# blinkm_mk2_3535ab.net
KiCad netlist of a schematic drawn in EAGLE
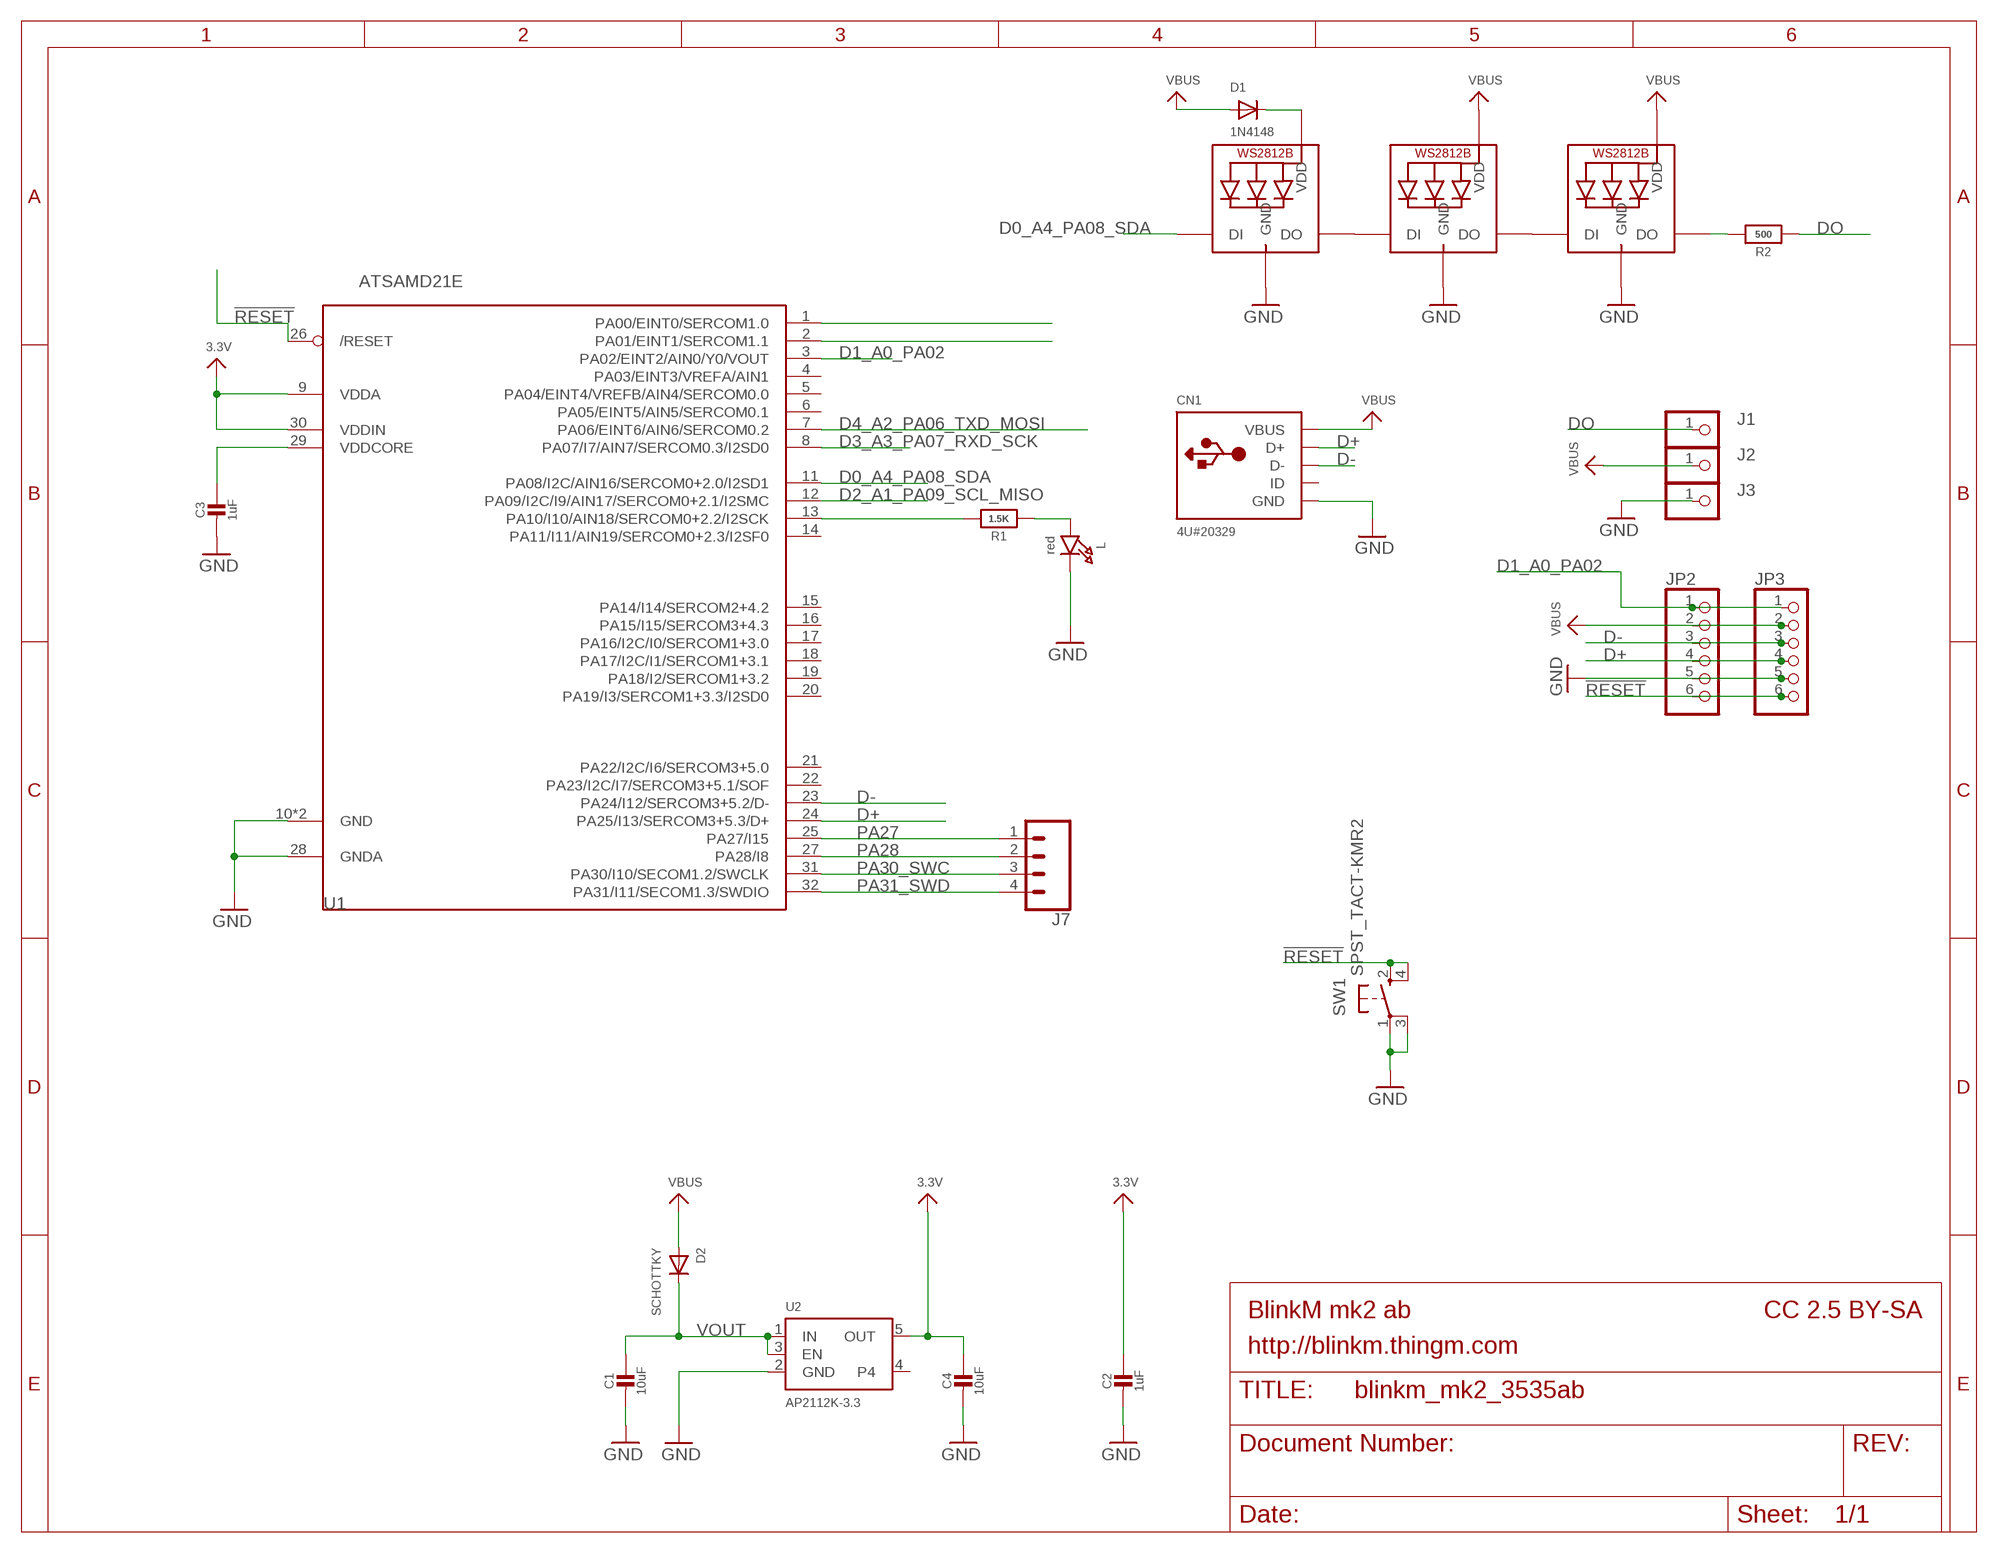
[diagram p0: schematic, sheet 1]

(export (version "E")
  (design (tool "Eeschema 10.0.6"))
  (components
    (comp (ref "C1")
      (value "10uF")
      (footprint "eagle-import:_0402")
      (libsource (lib "eagle-import") (part "CAP_CERAMIC_0402"))
    )
    (comp (ref "C2")
      (value "1uF")
      (footprint "eagle-import:_0402")
      (libsource (lib "eagle-import") (part "CAP_CERAMIC_0402"))
    )
    (comp (ref "C3")
      (value "1uF")
      (footprint "eagle-import:_0402")
      (libsource (lib "eagle-import") (part "CAP_CERAMIC_0402"))
    )
    (comp (ref "C4")
      (value "10uF")
      (footprint "eagle-import:_0402")
      (libsource (lib "eagle-import") (part "CAP_CERAMIC_0402"))
    )
    (comp (ref "CN1")
      (value "4U#20329")
      (footprint "eagle-import:4UCONN_20329_V2")
      (libsource (lib "eagle-import") (part "USB_MICRO_20329_V2"))
    )
    (comp (ref "D1")
      (value "1N4148")
      (footprint "eagle-import:SOD-523")
      (libsource (lib "eagle-import") (part "adafruit_420_DIODESOD-523"))
    )
    (comp (ref "D2")
      (value "SCHOTTKY")
      (footprint "eagle-import:SOD-523")
      (libsource (lib "eagle-import") (part "DIODESOD-523"))
    )
    (comp (ref "J1")
      (value "PINHD-1X1")
      (footprint "eagle-import:1X01")
      (libsource (lib "eagle-import") (part "PINHD-1X1"))
    )
    (comp (ref "J2")
      (value "PINHD-1X1")
      (footprint "eagle-import:1X01")
      (libsource (lib "eagle-import") (part "PINHD-1X1"))
    )
    (comp (ref "J3")
      (value "PINHD-1X1")
      (footprint "eagle-import:1X01")
      (libsource (lib "eagle-import") (part "PINHD-1X1"))
    )
    (comp (ref "J7")
      (value "CONN_041X04_NO_SILK")
      (footprint "eagle-import:1X04_NO_SILK")
      (libsource (lib "eagle-import") (part "CONN_041X04_NO_SILK"))
    )
    (comp (ref "JP2")
      (value "PINHD-1X6CLEAN")
      (footprint "eagle-import:1X06-CLEAN")
      (libsource (lib "eagle-import") (part "PINHD-1X6CLEAN"))
    )
    (comp (ref "JP3")
      (value "PINHD-1X6CLEAN")
      (footprint "eagle-import:1X06-CLEAN")
      (libsource (lib "eagle-import") (part "PINHD-1X6CLEAN"))
    )
    (comp (ref "L")
      (value "red")
      (footprint "eagle-import:CHIPLED_0603_NOOUTLINE")
      (libsource (lib "eagle-import") (part "LED0603_NOOUTLINE"))
    )
    (comp (ref "L1")
      (value "WS2812B3535")
      (footprint "eagle-import:LED3535")
      (libsource (lib "eagle-import") (part "WS2812B3535"))
    )
    (comp (ref "L2")
      (value "WS2812B3535")
      (footprint "eagle-import:LED3535")
      (libsource (lib "eagle-import") (part "WS2812B3535"))
    )
    (comp (ref "L3")
      (value "WS2812B3535")
      (footprint "eagle-import:LED3535")
      (libsource (lib "eagle-import") (part "WS2812B3535"))
    )
    (comp (ref "R1")
      (value "1.5K")
      (footprint "eagle-import:_0402")
      (libsource (lib "eagle-import") (part "RESISTOR_0402"))
    )
    (comp (ref "R2")
      (value "500")
      (footprint "eagle-import:_0402")
      (libsource (lib "eagle-import") (part "RESISTOR_0402"))
    )
    (comp (ref "SW1")
      (value "SPST_TACT-KMR2")
      (footprint "eagle-import:KMR2")
      (libsource (lib "eagle-import") (part "SPST_TACT-KMR2"))
    )
    (comp (ref "U1")
      (value "ATSAMD21E")
      (footprint "eagle-import:QFN32_5MM")
      (libsource (lib "eagle-import") (part "ATSAMD21E"))
    )
    (comp (ref "U2")
      (value "AP2112K-3.3")
      (footprint "eagle-import:SOT23-5")
      (libsource (lib "eagle-import") (part "VREG_SOT23-5"))
    )
  )
  (nets
    (net (code "1") (name "/D+") (class "Default")
      (node (ref "CN1") (pin "D+") (pinfunction "D+_D+") (pintype "bidirectional"))
      (node (ref "JP2") (pin "4") (pinfunction "4_4") (pintype "passive"))
      (node (ref "JP3") (pin "4") (pinfunction "4_4") (pintype "passive"))
      (node (ref "U1") (pin "24") (pinfunction "PA25/I13/SERCOM3+5.3/D+_24") (pintype "bidirectional"))
    )
    (net (code "2") (name "/D-") (class "Default")
      (node (ref "CN1") (pin "D-") (pinfunction "D-_D-") (pintype "bidirectional"))
      (node (ref "JP2") (pin "3") (pinfunction "3_3") (pintype "passive"))
      (node (ref "JP3") (pin "3") (pinfunction "3_3") (pintype "passive"))
      (node (ref "U1") (pin "23") (pinfunction "PA24/I12/SERCOM3+5.2/D-_23") (pintype "bidirectional"))
    )
    (net (code "3") (name "/D0_A4_PA08_SDA") (class "Default")
      (node (ref "L1") (pin "1") (pinfunction "DI_1") (pintype "input"))
      (node (ref "U1") (pin "11") (pinfunction "PA08/I2C/AIN16/SERCOM0+2.0/I2SD1_11") (pintype "bidirectional"))
    )
    (net (code "4") (name "/D1_A0_PA02") (class "Default")
      (node (ref "JP2") (pin "1") (pinfunction "1_1") (pintype "passive"))
      (node (ref "JP3") (pin "1") (pinfunction "1_1") (pintype "passive"))
      (node (ref "U1") (pin "3") (pinfunction "PA02/EINT2/AIN0/Y0/VOUT_3") (pintype "bidirectional"))
    )
    (net (code "5") (name "/D2_A1_PA09_SCL_MISO") (class "Default")
      (node (ref "U1") (pin "12") (pinfunction "PA09/I2C/I9/AIN17/SERCOM0+2.1/I2SMC_12") (pintype "bidirectional"))
    )
    (net (code "6") (name "/D3_A3_PA07_RXD_SCK") (class "Default")
      (node (ref "U1") (pin "8") (pinfunction "PA07/I7/AIN7/SERCOM0.3/I2SD0_8") (pintype "bidirectional"))
    )
    (net (code "7") (name "/D4_A2_PA06_TXD_MOSI") (class "Default")
      (node (ref "U1") (pin "7") (pinfunction "PA06/EINT6/AIN6/SERCOM0.2_7") (pintype "bidirectional"))
    )
    (net (code "8") (name "/DO") (class "Default")
      (node (ref "J1") (pin "1") (pinfunction "1_1") (pintype "passive"))
      (node (ref "R2") (pin "1") (pinfunction "1_1") (pintype "passive"))
    )
    (net (code "9") (name "/PA27") (class "Default")
      (node (ref "J7") (pin "1") (pinfunction "1_1") (pintype "passive"))
      (node (ref "U1") (pin "25") (pinfunction "PA27/I15_25") (pintype "bidirectional"))
    )
    (net (code "10") (name "/PA28") (class "Default")
      (node (ref "J7") (pin "2") (pinfunction "2_2") (pintype "passive"))
      (node (ref "U1") (pin "27") (pinfunction "PA28/I8_27") (pintype "bidirectional"))
    )
    (net (code "11") (name "/PA30_SWC") (class "Default")
      (node (ref "J7") (pin "3") (pinfunction "3_3") (pintype "passive"))
      (node (ref "U1") (pin "31") (pinfunction "PA30/I10/SECOM1.2/SWCLK_31") (pintype "bidirectional"))
    )
    (net (code "12") (name "/PA31_SWD") (class "Default")
      (node (ref "J7") (pin "4") (pinfunction "4_4") (pintype "passive"))
      (node (ref "U1") (pin "32") (pinfunction "PA31/I11/SECOM1.3/SWDIO_32") (pintype "bidirectional"))
    )
    (net (code "13") (name "/VOUT") (class "Default")
      (node (ref "C1") (pin "1") (pinfunction "1_1") (pintype "passive"))
      (node (ref "D2") (pin "K") (pinfunction "C_K") (pintype "passive"))
      (node (ref "U2") (pin "1") (pinfunction "IN_1") (pintype "power_in"))
      (node (ref "U2") (pin "3") (pinfunction "EN_3") (pintype "input"))
    )
    (net (code "14") (name "/~{RESET}") (class "Default")
      (node (ref "JP2") (pin "6") (pinfunction "6_6") (pintype "passive"))
      (node (ref "JP3") (pin "6") (pinfunction "6_6") (pintype "passive"))
      (node (ref "SW1") (pin "2") (pinfunction "S_2") (pintype "passive"))
      (node (ref "SW1") (pin "4") (pinfunction "S1_4") (pintype "passive"))
      (node (ref "U1") (pin "26") (pinfunction "/RESET_26") (pintype "bidirectional"))
    )
    (net (code "15") (name "3.3V") (class "Default")
      (node (ref "C2") (pin "1") (pinfunction "1_1") (pintype "passive"))
      (node (ref "C4") (pin "1") (pinfunction "1_1") (pintype "passive"))
      (node (ref "U1") (pin "30") (pinfunction "VDDIN_30") (pintype "power_in"))
      (node (ref "U1") (pin "9") (pinfunction "VDDA_9") (pintype "power_in"))
      (node (ref "U2") (pin "5") (pinfunction "OUT_5") (pintype "power_in"))
    )
    (net (code "16") (name "GND") (class "Default")
      (node (ref "C1") (pin "2") (pinfunction "2_2") (pintype "passive"))
      (node (ref "C2") (pin "2") (pinfunction "2_2") (pintype "passive"))
      (node (ref "C3") (pin "2") (pinfunction "2_2") (pintype "passive"))
      (node (ref "C4") (pin "2") (pinfunction "2_2") (pintype "passive"))
      (node (ref "CN1") (pin "BASE@1") (pinfunction "GND_BASE@1") (pintype "power_in"))
      (node (ref "CN1") (pin "BASE@2") (pinfunction "GND_BASE@2") (pintype "power_in"))
      (node (ref "CN1") (pin "GND") (pinfunction "GND_GND") (pintype "power_in"))
      (node (ref "CN1") (pin "SPRT@1") (pinfunction "GND_SPRT@1") (pintype "power_in"))
      (node (ref "CN1") (pin "SPRT@2") (pinfunction "GND_SPRT@2") (pintype "power_in"))
      (node (ref "CN1") (pin "SPRT@3") (pinfunction "GND_SPRT@3") (pintype "power_in"))
      (node (ref "CN1") (pin "SPRT@4") (pinfunction "GND_SPRT@4") (pintype "power_in"))
      (node (ref "J3") (pin "1") (pinfunction "1_1") (pintype "passive"))
      (node (ref "JP2") (pin "5") (pinfunction "5_5") (pintype "passive"))
      (node (ref "JP3") (pin "5") (pinfunction "5_5") (pintype "passive"))
      (node (ref "L") (pin "C") (pinfunction "C_C") (pintype "passive"))
      (node (ref "L1") (pin "4") (pinfunction "GND_4") (pintype "power_in"))
      (node (ref "L2") (pin "4") (pinfunction "GND_4") (pintype "power_in"))
      (node (ref "L3") (pin "4") (pinfunction "GND_4") (pintype "power_in"))
      (node (ref "SW1") (pin "1") (pinfunction "P_1") (pintype "passive"))
      (node (ref "SW1") (pin "3") (pinfunction "P1_3") (pintype "passive"))
      (node (ref "U1") (pin "10") (pinfunction "GND_10") (pintype "power_in"))
      (node (ref "U1") (pin "28") (pinfunction "GNDA_28") (pintype "power_in"))
      (node (ref "U1") (pin "33") (pinfunction "GND_33") (pintype "power_in"))
      (node (ref "U2") (pin "2") (pinfunction "GND_2") (pintype "power_in"))
    )
    (net (code "17") (name "Net-(D1-C)") (class "Default")
      (node (ref "D1") (pin "K") (pinfunction "C_K") (pintype "passive"))
      (node (ref "L1") (pin "2") (pinfunction "VDD_2") (pintype "power_in"))
    )
    (net (code "18") (name "Net-(L-PadA)") (class "Default")
      (node (ref "L") (pin "A") (pinfunction "A_A") (pintype "passive"))
      (node (ref "R1") (pin "1") (pinfunction "1_1") (pintype "passive"))
    )
    (net (code "19") (name "Net-(L1-DO)") (class "Default")
      (node (ref "L1") (pin "3") (pinfunction "DO_3") (pintype "output"))
      (node (ref "L2") (pin "1") (pinfunction "DI_1") (pintype "input"))
    )
    (net (code "20") (name "Net-(L2-DO)") (class "Default")
      (node (ref "L2") (pin "3") (pinfunction "DO_3") (pintype "output"))
      (node (ref "L3") (pin "1") (pinfunction "DI_1") (pintype "input"))
    )
    (net (code "21") (name "Net-(L3-DO)") (class "Default")
      (node (ref "L3") (pin "3") (pinfunction "DO_3") (pintype "output"))
      (node (ref "R2") (pin "2") (pinfunction "2_2") (pintype "passive"))
    )
    (net (code "22") (name "Net-(U1-PA10{slash}I10{slash}AIN18{slash}SERCOM0+2.2{slash}I2SCK)") (class "Default")
      (node (ref "R1") (pin "2") (pinfunction "2_2") (pintype "passive"))
      (node (ref "U1") (pin "13") (pinfunction "PA10/I10/AIN18/SERCOM0+2.2/I2SCK_13") (pintype "bidirectional"))
    )
    (net (code "23") (name "Net-(U1-VDDCORE)") (class "Default")
      (node (ref "C3") (pin "1") (pinfunction "1_1") (pintype "passive"))
      (node (ref "U1") (pin "29") (pinfunction "VDDCORE_29") (pintype "power_in"))
    )
    (net (code "24") (name "VBUS") (class "Default")
      (node (ref "CN1") (pin "VBUS") (pinfunction "VBUS_VBUS") (pintype "power_in"))
      (node (ref "D1") (pin "A") (pinfunction "A_A") (pintype "passive"))
      (node (ref "D2") (pin "A") (pinfunction "A_A") (pintype "passive"))
      (node (ref "J2") (pin "1") (pinfunction "1_1") (pintype "passive"))
      (node (ref "JP2") (pin "2") (pinfunction "2_2") (pintype "passive"))
      (node (ref "JP3") (pin "2") (pinfunction "2_2") (pintype "passive"))
      (node (ref "L2") (pin "2") (pinfunction "VDD_2") (pintype "power_in"))
      (node (ref "L3") (pin "2") (pinfunction "VDD_2") (pintype "power_in"))
    )
    (net (code "25") (name "unconnected-(CN1-PadID)") (class "Default")
      (node (ref "CN1") (pin "ID") (pinfunction "ID_ID") (pintype "bidirectional"))
    )
    (net (code "26") (name "unconnected-(U1-PA00{slash}EINT0{slash}SERCOM1.0-Pad1)") (class "Default")
      (node (ref "U1") (pin "1") (pinfunction "PA00/EINT0/SERCOM1.0_1") (pintype "bidirectional"))
    )
    (net (code "27") (name "unconnected-(U1-PA01{slash}EINT1{slash}SERCOM1.1-Pad2)") (class "Default")
      (node (ref "U1") (pin "2") (pinfunction "PA01/EINT1/SERCOM1.1_2") (pintype "bidirectional"))
    )
    (net (code "28") (name "unconnected-(U1-PA03{slash}EINT3{slash}VREFA{slash}AIN1-Pad4)") (class "Default")
      (node (ref "U1") (pin "4") (pinfunction "PA03/EINT3/VREFA/AIN1_4") (pintype "bidirectional"))
    )
    (net (code "29") (name "unconnected-(U1-PA04{slash}EINT4{slash}VREFB{slash}AIN4{slash}SERCOM0.0-Pad5)") (class "Default")
      (node (ref "U1") (pin "5") (pinfunction "PA04/EINT4/VREFB/AIN4/SERCOM0.0_5") (pintype "bidirectional"))
    )
    (net (code "30") (name "unconnected-(U1-PA05{slash}EINT5{slash}AIN5{slash}SERCOM0.1-Pad6)") (class "Default")
      (node (ref "U1") (pin "6") (pinfunction "PA05/EINT5/AIN5/SERCOM0.1_6") (pintype "bidirectional"))
    )
    (net (code "31") (name "unconnected-(U1-PA11{slash}I11{slash}AIN19{slash}SERCOM0+2.3{slash}I2SF0-Pad14)") (class "Default")
      (node (ref "U1") (pin "14") (pinfunction "PA11/I11/AIN19/SERCOM0+2.3/I2SF0_14") (pintype "bidirectional"))
    )
    (net (code "32") (name "unconnected-(U1-PA14{slash}I14{slash}SERCOM2+4.2-Pad15)") (class "Default")
      (node (ref "U1") (pin "15") (pinfunction "PA14/I14/SERCOM2+4.2_15") (pintype "bidirectional"))
    )
    (net (code "33") (name "unconnected-(U1-PA15{slash}I15{slash}SERCOM3+4.3-Pad16)") (class "Default")
      (node (ref "U1") (pin "16") (pinfunction "PA15/I15/SERCOM3+4.3_16") (pintype "bidirectional"))
    )
    (net (code "34") (name "unconnected-(U1-PA16{slash}I2C{slash}I0{slash}SERCOM1+3.0-Pad17)") (class "Default")
      (node (ref "U1") (pin "17") (pinfunction "PA16/I2C/I0/SERCOM1+3.0_17") (pintype "bidirectional"))
    )
    (net (code "35") (name "unconnected-(U1-PA17{slash}I2C{slash}I1{slash}SERCOM1+3.1-Pad18)") (class "Default")
      (node (ref "U1") (pin "18") (pinfunction "PA17/I2C/I1/SERCOM1+3.1_18") (pintype "bidirectional"))
    )
    (net (code "36") (name "unconnected-(U1-PA18{slash}I2{slash}SERCOM1+3.2-Pad19)") (class "Default")
      (node (ref "U1") (pin "19") (pinfunction "PA18/I2/SERCOM1+3.2_19") (pintype "bidirectional"))
    )
    (net (code "37") (name "unconnected-(U1-PA19{slash}I3{slash}SERCOM1+3.3{slash}I2SD0-Pad20)") (class "Default")
      (node (ref "U1") (pin "20") (pinfunction "PA19/I3/SERCOM1+3.3/I2SD0_20") (pintype "bidirectional"))
    )
    (net (code "38") (name "unconnected-(U1-PA22{slash}I2C{slash}I6{slash}SERCOM3+5.0-Pad21)") (class "Default")
      (node (ref "U1") (pin "21") (pinfunction "PA22/I2C/I6/SERCOM3+5.0_21") (pintype "bidirectional"))
    )
    (net (code "39") (name "unconnected-(U1-PA23{slash}I2C{slash}I7{slash}SERCOM3+5.1{slash}SOF-Pad22)") (class "Default")
      (node (ref "U1") (pin "22") (pinfunction "PA23/I2C/I7/SERCOM3+5.1/SOF_22") (pintype "bidirectional"))
    )
    (net (code "40") (name "unconnected-(U2-P4-Pad4)") (class "Default")
      (node (ref "U2") (pin "4") (pinfunction "P4_4") (pintype "bidirectional"))
    )
  )
)
